# mk312lite_V2.net
KiCad netlist of a schematic drawn in EAGLE
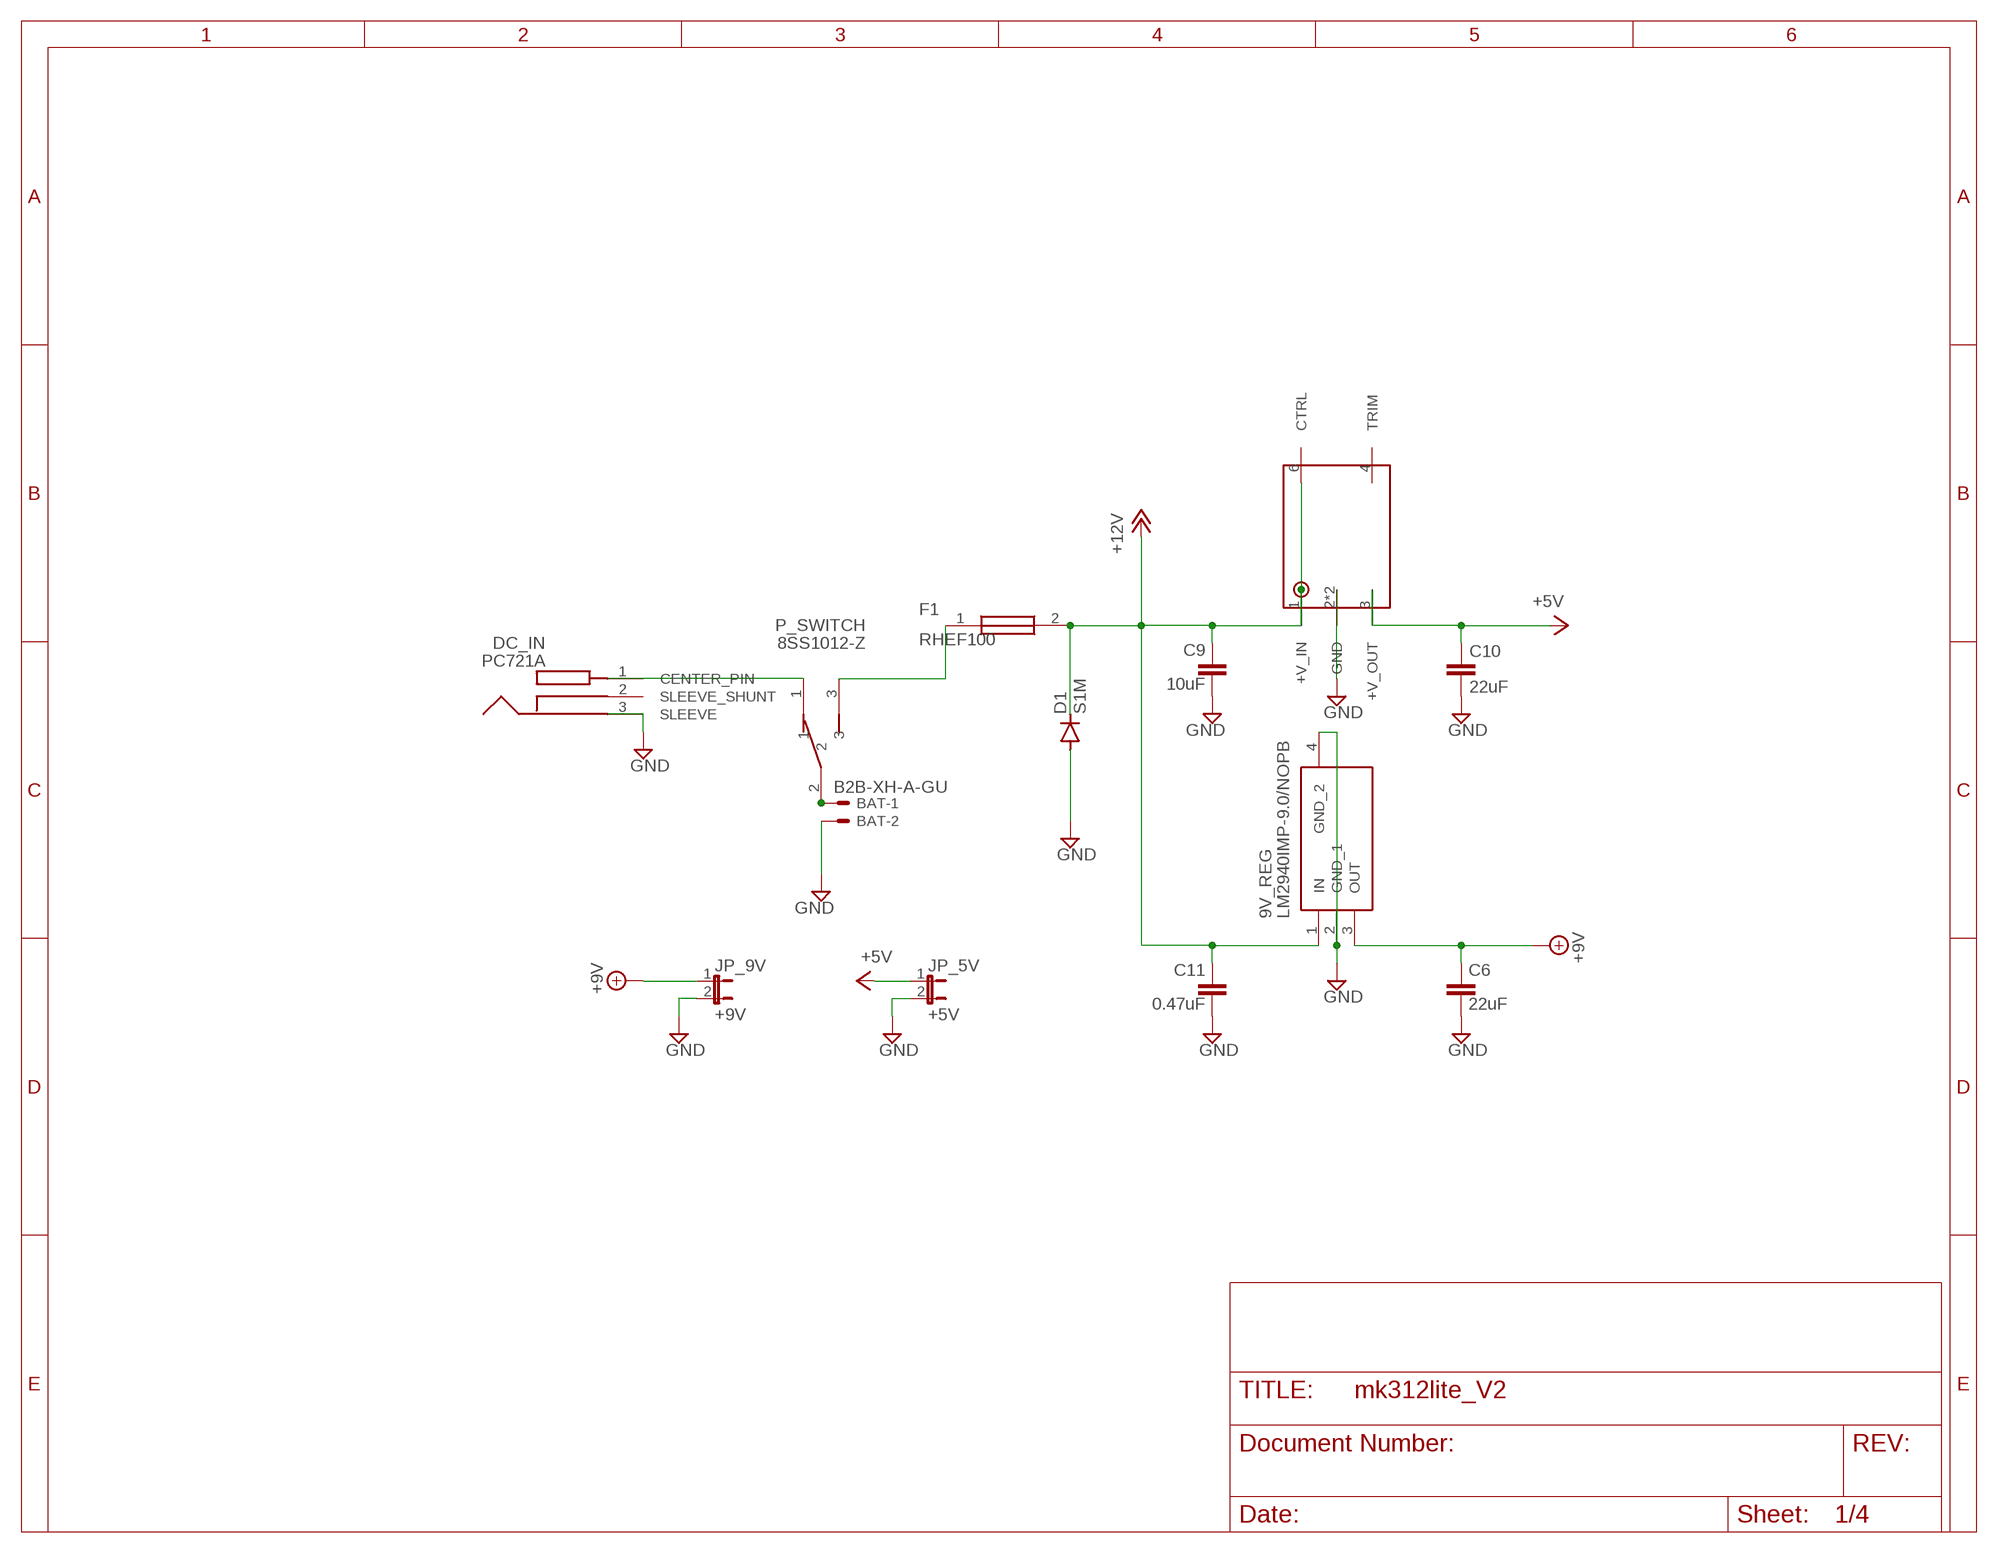
[diagram p0: schematic, sheet 1]
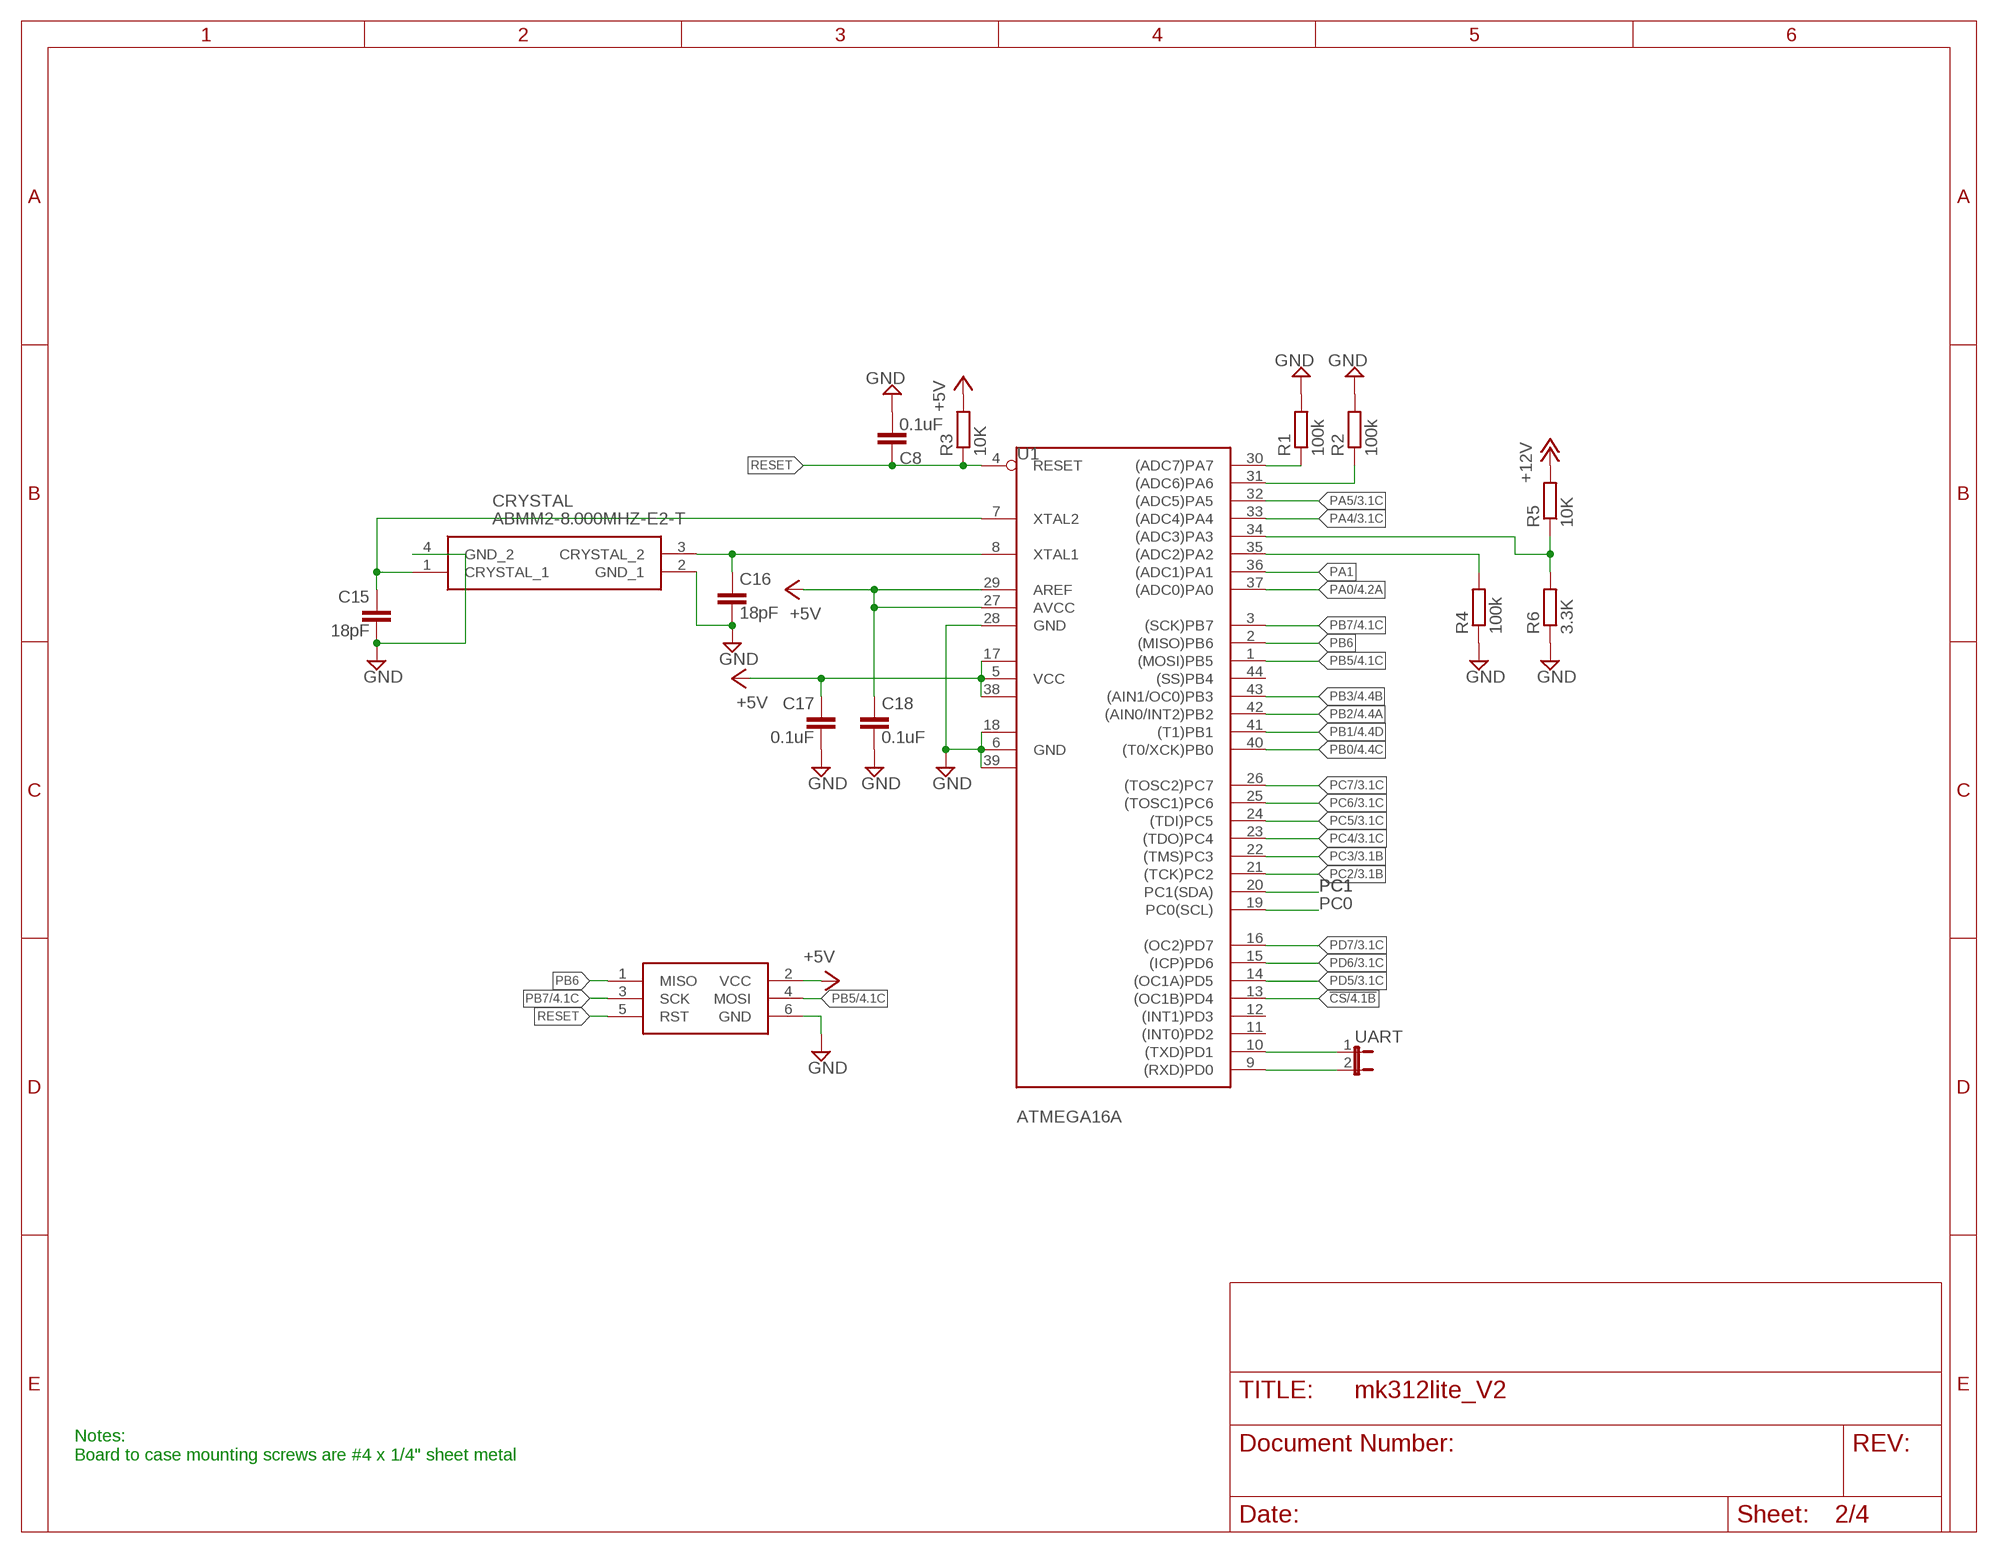
[diagram p1: schematic, sheet 2]
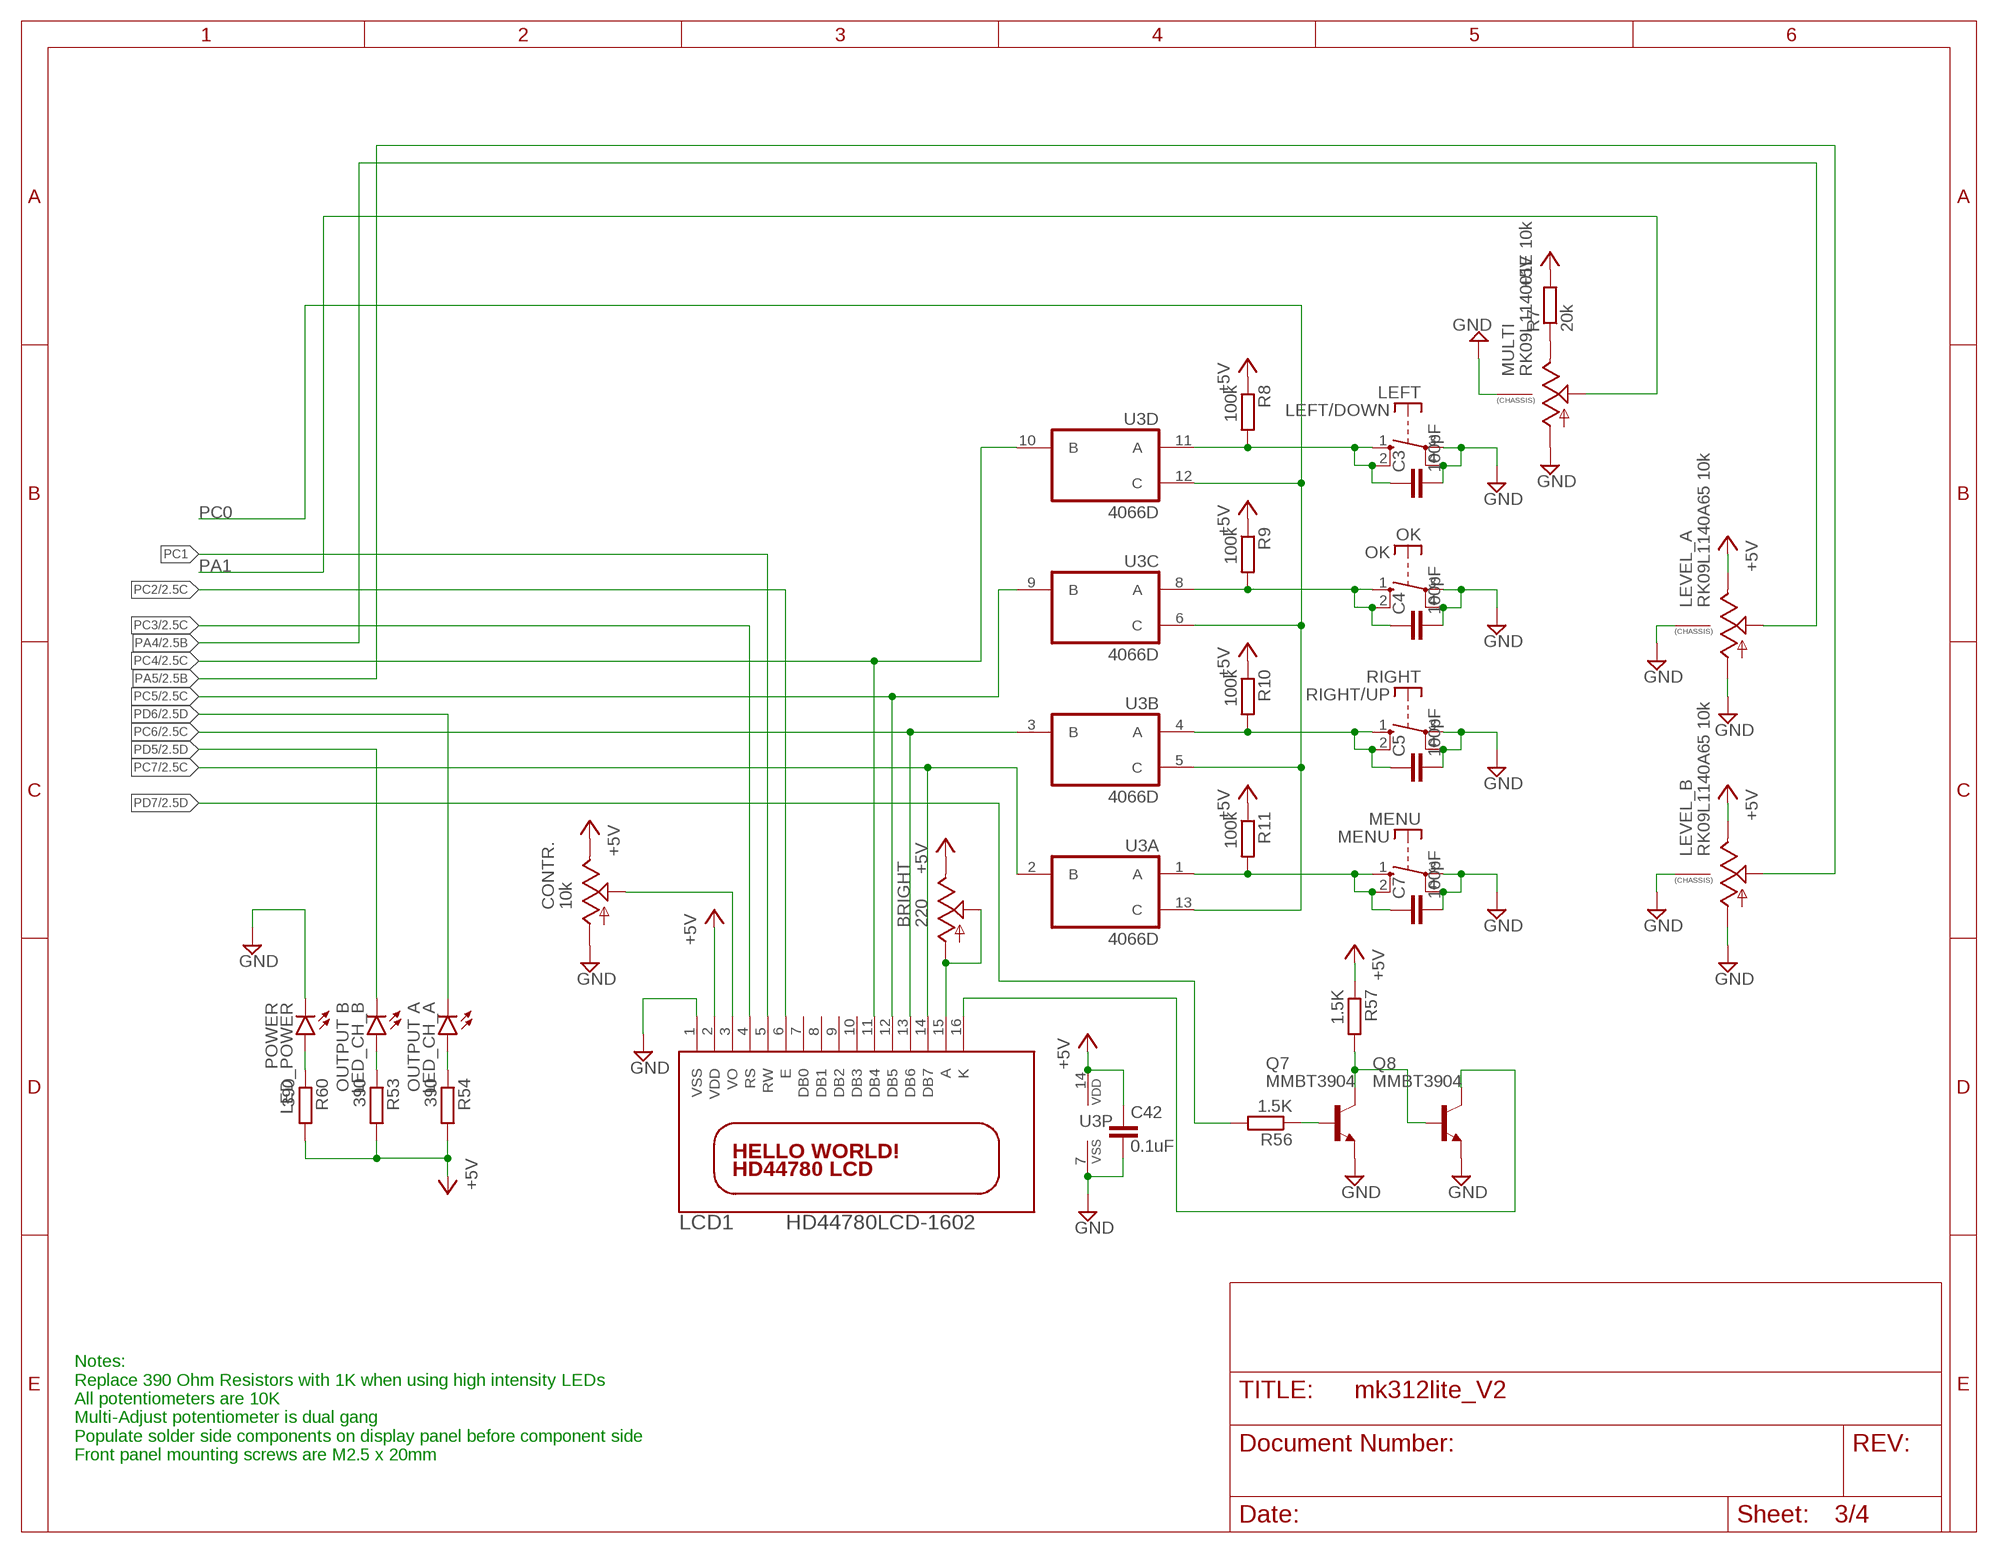
[diagram p2: schematic, sheet 3]
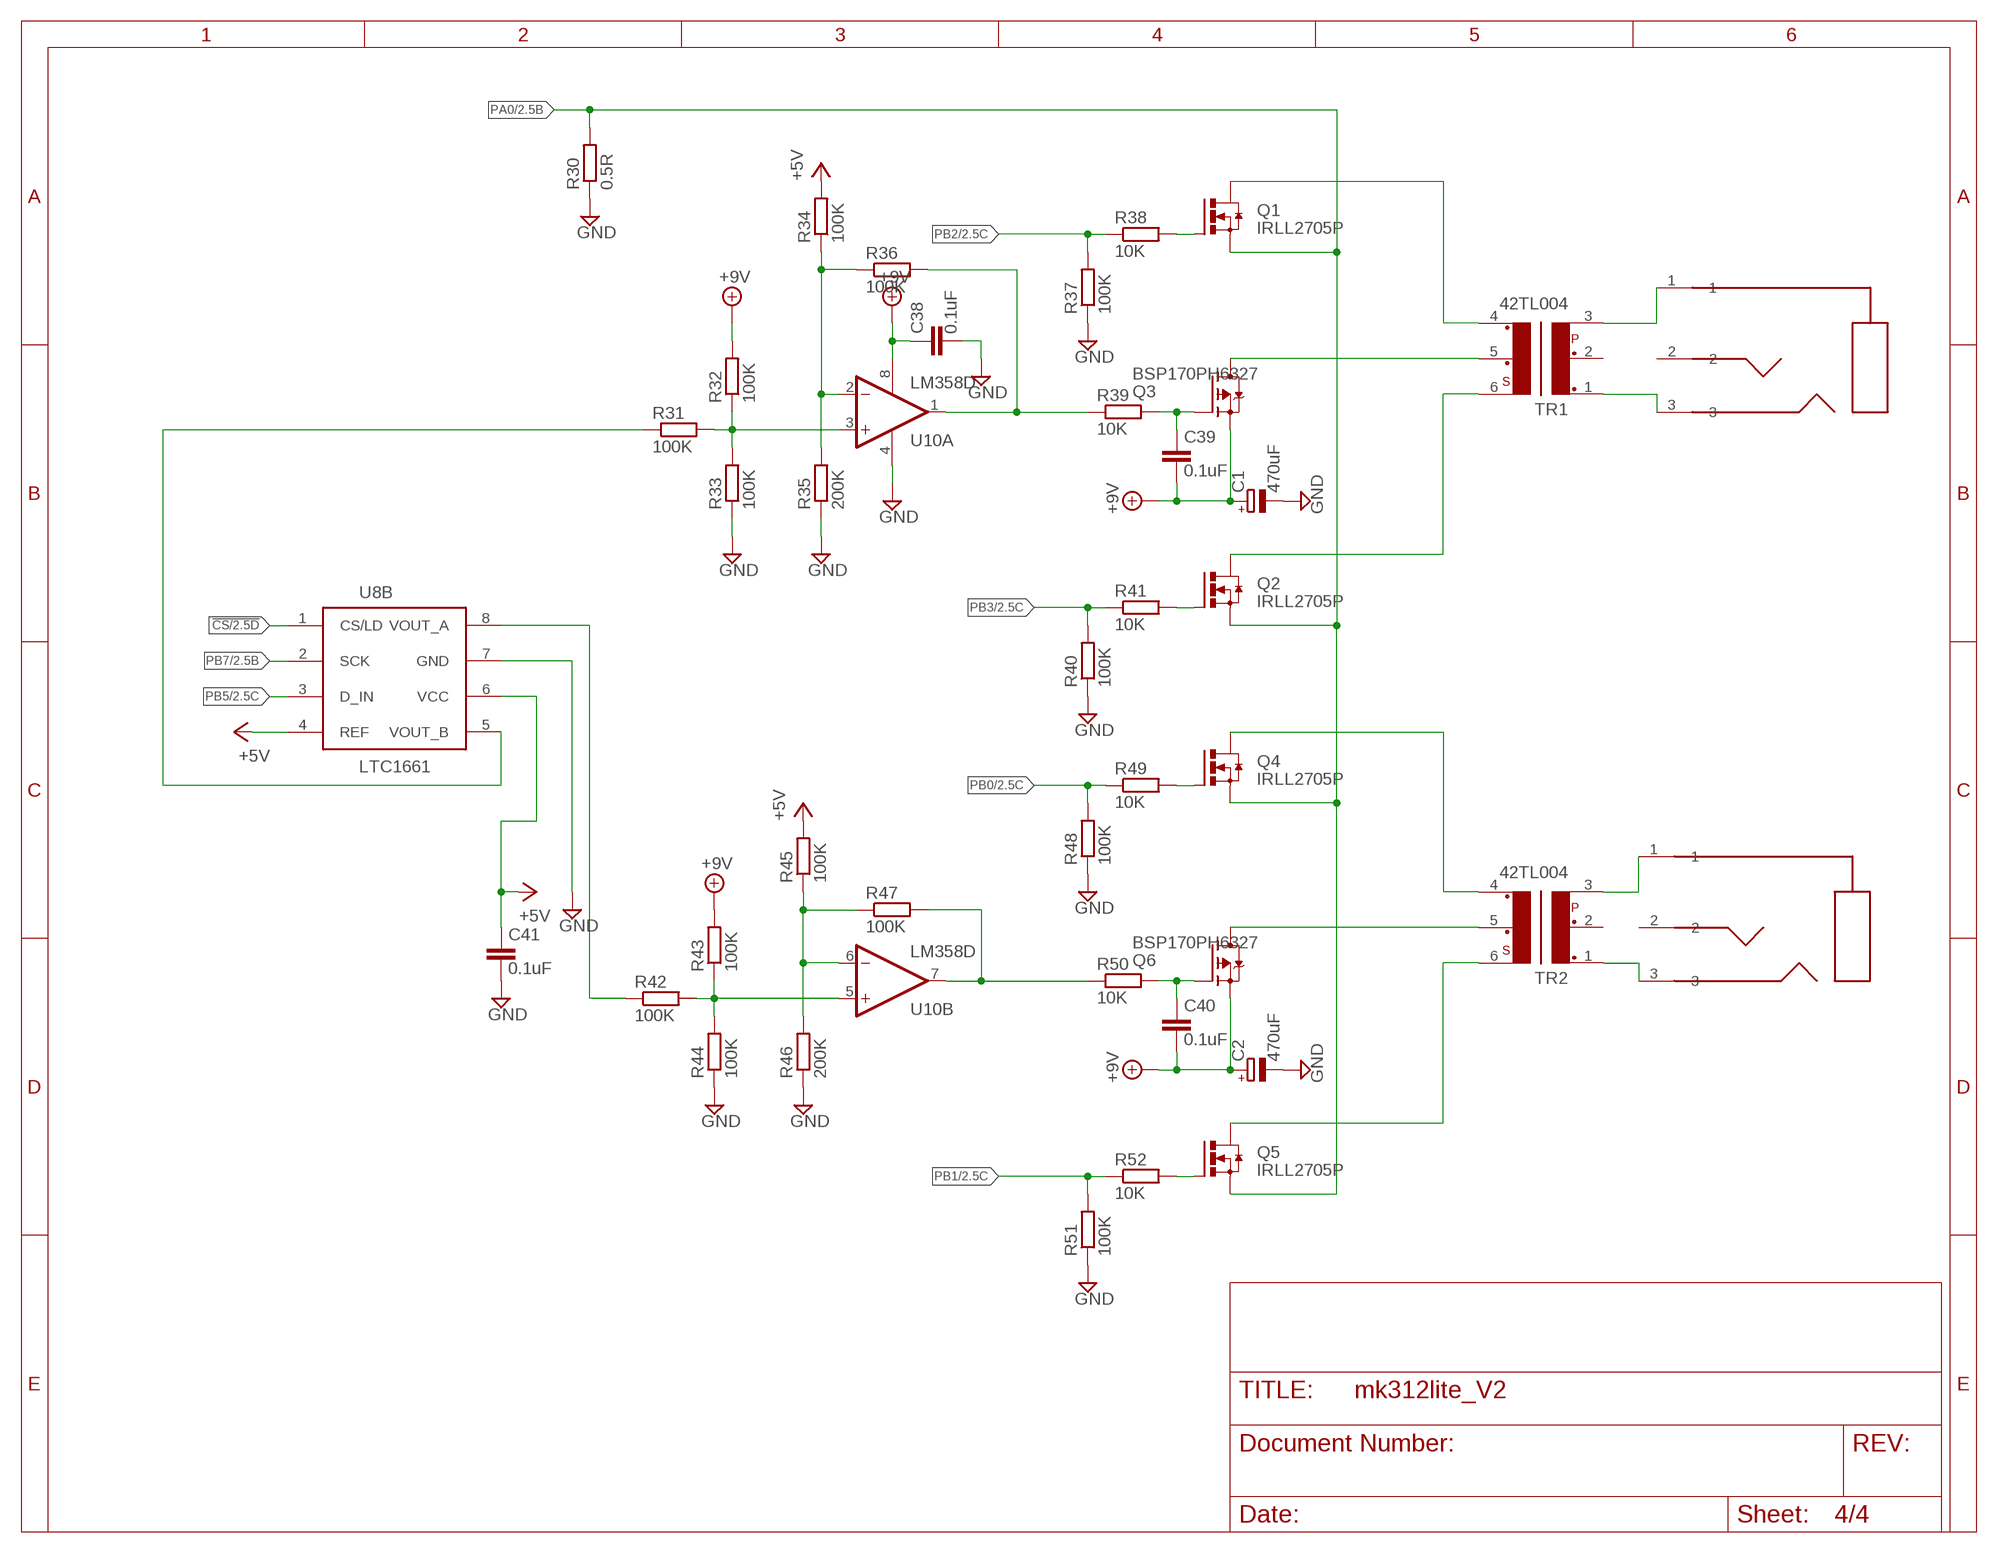
[diagram p3: schematic, sheet 4]

(export (version "E")
  (design (tool "Eeschema 10.0.6"))
  (components
    (comp (ref "C8")
      (value "0.1uF")
      (footprint "eagle-import:C0805")
      (libsource (lib "eagle-import") (part "C-EUC0805"))
    )
    (comp (ref "C15")
      (value "18pF")
      (footprint "eagle-import:C0805")
      (libsource (lib "eagle-import") (part "C-EUC0805"))
    )
    (comp (ref "C16")
      (value "18pF")
      (footprint "eagle-import:C0805")
      (libsource (lib "eagle-import") (part "C-EUC0805"))
    )
    (comp (ref "C17")
      (value "0.1uF")
      (footprint "eagle-import:C0805")
      (libsource (lib "eagle-import") (part "C-EUC0805"))
    )
    (comp (ref "C18")
      (value "0.1uF")
      (footprint "eagle-import:C0805")
      (libsource (lib "eagle-import") (part "C-EUC0805"))
    )
    (comp (ref "CRYSTAL")
      (value "ABMM2-8.000MHZ-E2-T")
      (footprint "eagle-import:ABMM2")
      (fields (field (name "MOUSER_PART_NUMBER") "815-ABMM2-8-E2T"))
      (libsource (lib "eagle-import") (part "ABMM2-8.000MHZ-E2-T"))
    )
    (comp (ref "ISP1")
      (value "AVRISP-6")
      (footprint "eagle-import:AVRISP")
      (libsource (lib "eagle-import") (part "AVRISP-6"))
    )
    (comp (ref "R1")
      (value "100k")
      (footprint "eagle-import:R0805")
      (libsource (lib "eagle-import") (part "R-EU_R0805"))
    )
    (comp (ref "R2")
      (value "100k")
      (footprint "eagle-import:R0805")
      (libsource (lib "eagle-import") (part "R-EU_R0805"))
    )
    (comp (ref "R3")
      (value "10K")
      (footprint "eagle-import:R0805")
      (libsource (lib "eagle-import") (part "R-EU_R0805"))
    )
    (comp (ref "R4")
      (value "100k")
      (footprint "eagle-import:R0805")
      (libsource (lib "eagle-import") (part "R-EU_R0805"))
    )
    (comp (ref "R5")
      (value "10K")
      (footprint "eagle-import:R0805")
      (libsource (lib "eagle-import") (part "R-EU_R0805"))
    )
    (comp (ref "R6")
      (value "3.3K")
      (footprint "eagle-import:R0805")
      (libsource (lib "eagle-import") (part "R-EU_R0805"))
    )
    (comp (ref "U1")
      (value "ATMEGA16A")
      (footprint "eagle-import:TQFP44")
      (fields (field (name "MPN") "ATMEGA16-16AU"))
      (libsource (lib "eagle-import") (part "MEGA16-A"))
    )
    (comp (ref "UART")
      (value "JP1E")
      (footprint "eagle-import:JP1")
      (libsource (lib "eagle-import") (part "jumper_252_JP1E"))
    )
    (comp (ref "C1")
      (value "470uF")
      (footprint "eagle-import:150CLZ-1010")
      (libsource (lib "eagle-import") (part "CPOL-EU150CLZ-1010"))
    )
    (comp (ref "C2")
      (value "470uF")
      (footprint "eagle-import:150CLZ-1010")
      (libsource (lib "eagle-import") (part "CPOL-EU150CLZ-1010"))
    )
    (comp (ref "C38")
      (value "0.1uF")
      (footprint "eagle-import:C0805")
      (libsource (lib "eagle-import") (part "C-EUC0805"))
    )
    (comp (ref "C39")
      (value "0.1uF")
      (footprint "eagle-import:C0805")
      (libsource (lib "eagle-import") (part "C-EUC0805"))
    )
    (comp (ref "C40")
      (value "0.1uF")
      (footprint "eagle-import:C0805")
      (libsource (lib "eagle-import") (part "C-EUC0805"))
    )
    (comp (ref "C41")
      (value "0.1uF")
      (footprint "eagle-import:C0805")
      (libsource (lib "eagle-import") (part "C-EUC0805"))
    )
    (comp (ref "CHAN_A")
      (value "PJ-301C")
      (footprint "eagle-import:PJ-301C")
      (libsource (lib "eagle-import") (part "PC-301C"))
    )
    (comp (ref "CHAN_B")
      (value "PJ-301C")
      (footprint "eagle-import:PJ-301C")
      (libsource (lib "eagle-import") (part "PC-301C"))
    )
    (comp (ref "Q1")
      (value "IRLL2705P")
      (footprint "eagle-import:SOT223")
      (libsource (lib "eagle-import") (part "N-HEXFET-2D_?-SOT232IRLL2705"))
    )
    (comp (ref "Q2")
      (value "IRLL2705P")
      (footprint "eagle-import:SOT223")
      (libsource (lib "eagle-import") (part "N-HEXFET-2D_?-SOT232IRLL2705"))
    )
    (comp (ref "Q3")
      (value "BSP170PH6327")
      (footprint "eagle-import:SOT230P700X180-4N")
      (libsource (lib "eagle-import") (part "IRFL9014TRPBF"))
    )
    (comp (ref "Q4")
      (value "IRLL2705P")
      (footprint "eagle-import:SOT223")
      (libsource (lib "eagle-import") (part "N-HEXFET-2D_?-SOT232IRLL2705"))
    )
    (comp (ref "Q5")
      (value "IRLL2705P")
      (footprint "eagle-import:SOT223")
      (libsource (lib "eagle-import") (part "N-HEXFET-2D_?-SOT232IRLL2705"))
    )
    (comp (ref "Q6")
      (value "BSP170PH6327")
      (footprint "eagle-import:SOT230P700X180-4N")
      (libsource (lib "eagle-import") (part "IRFL9014TRPBF"))
    )
    (comp (ref "R30")
      (value "0.5R")
      (footprint "eagle-import:R1210")
      (libsource (lib "eagle-import") (part "R-EU_R1210"))
    )
    (comp (ref "R31")
      (value "100K")
      (footprint "eagle-import:R0805")
      (libsource (lib "eagle-import") (part "R-EU_R0805"))
    )
    (comp (ref "R32")
      (value "100K")
      (footprint "eagle-import:R0805")
      (libsource (lib "eagle-import") (part "R-EU_R0805"))
    )
    (comp (ref "R33")
      (value "100K")
      (footprint "eagle-import:R0805")
      (libsource (lib "eagle-import") (part "R-EU_R0805"))
    )
    (comp (ref "R34")
      (value "100K")
      (footprint "eagle-import:R0805")
      (libsource (lib "eagle-import") (part "R-EU_R0805"))
    )
    (comp (ref "R35")
      (value "200K")
      (footprint "eagle-import:R0805")
      (libsource (lib "eagle-import") (part "R-EU_R0805"))
    )
    (comp (ref "R36")
      (value "100K")
      (footprint "eagle-import:R0805")
      (libsource (lib "eagle-import") (part "R-EU_R0805"))
    )
    (comp (ref "R37")
      (value "100K")
      (footprint "eagle-import:R0805")
      (libsource (lib "eagle-import") (part "R-EU_R0805"))
    )
    (comp (ref "R38")
      (value "10K")
      (footprint "eagle-import:R0805")
      (libsource (lib "eagle-import") (part "R-EU_R0805"))
    )
    (comp (ref "R39")
      (value "10K")
      (footprint "eagle-import:R0805")
      (libsource (lib "eagle-import") (part "R-EU_R0805"))
    )
    (comp (ref "R40")
      (value "100K")
      (footprint "eagle-import:R0805")
      (libsource (lib "eagle-import") (part "R-EU_R0805"))
    )
    (comp (ref "R41")
      (value "10K")
      (footprint "eagle-import:R0805")
      (libsource (lib "eagle-import") (part "R-EU_R0805"))
    )
    (comp (ref "R42")
      (value "100K")
      (footprint "eagle-import:R0805")
      (libsource (lib "eagle-import") (part "R-EU_R0805"))
    )
    (comp (ref "R43")
      (value "100K")
      (footprint "eagle-import:R0805")
      (libsource (lib "eagle-import") (part "R-EU_R0805"))
    )
    (comp (ref "R44")
      (value "100K")
      (footprint "eagle-import:R0805")
      (libsource (lib "eagle-import") (part "R-EU_R0805"))
    )
    (comp (ref "R45")
      (value "100K")
      (footprint "eagle-import:R0805")
      (libsource (lib "eagle-import") (part "R-EU_R0805"))
    )
    (comp (ref "R46")
      (value "200K")
      (footprint "eagle-import:R0805")
      (libsource (lib "eagle-import") (part "R-EU_R0805"))
    )
    (comp (ref "R47")
      (value "100K")
      (footprint "eagle-import:R0805")
      (libsource (lib "eagle-import") (part "R-EU_R0805"))
    )
    (comp (ref "R48")
      (value "100K")
      (footprint "eagle-import:R0805")
      (libsource (lib "eagle-import") (part "R-EU_R0805"))
    )
    (comp (ref "R49")
      (value "10K")
      (footprint "eagle-import:R0805")
      (libsource (lib "eagle-import") (part "R-EU_R0805"))
    )
    (comp (ref "R50")
      (value "10K")
      (footprint "eagle-import:R0805")
      (libsource (lib "eagle-import") (part "R-EU_R0805"))
    )
    (comp (ref "R51")
      (value "100K")
      (footprint "eagle-import:R0805")
      (libsource (lib "eagle-import") (part "R-EU_R0805"))
    )
    (comp (ref "R52")
      (value "10K")
      (footprint "eagle-import:R0805")
      (libsource (lib "eagle-import") (part "R-EU_R0805"))
    )
    (comp (ref "TR1")
      (value "42TL004")
      (footprint "eagle-import:42TL")
      (libsource (lib "eagle-import") (part "42T?L023"))
    )
    (comp (ref "TR2")
      (value "42TL004")
      (footprint "eagle-import:42TL")
      (libsource (lib "eagle-import") (part "42T?L023"))
    )
    (comp (ref "U8B")
      (value "LTC1661")
      (footprint "eagle-import:MSOP8")
      (libsource (lib "eagle-import") (part "LTC1661IMS8"))
    )
    (comp (ref "U10")
      (value "LM358D")
      (footprint "eagle-import:SO08")
      (libsource (lib "eagle-import") (part "LM358D"))
    )
    (comp (ref "9V_REG")
      (value "LM2940IMP-9.0/NOPB")
      (footprint "eagle-import:SOT230P700X180-4N")
      (fields (field (name "MOUSER_PART_NUMBER") "926-LM2940IMP90NOPB"))
      (libsource (lib "eagle-import") (part "LM2940IMP-9.0_NOPB"))
    )
    (comp (ref "BAT")
      (value "B2B-XH-A-GU")
      (footprint "eagle-import:JST-XH-02-PACKAGE-LONG-PAD")
      (libsource (lib "eagle-import") (part "JST-XH-02-PIN-LONG-PAD"))
    )
    (comp (ref "C6")
      (value "22uF")
      (footprint "eagle-import:C1206")
      (libsource (lib "eagle-import") (part "C-EUC1206"))
    )
    (comp (ref "C9")
      (value "10uF")
      (footprint "eagle-import:C0805")
      (libsource (lib "eagle-import") (part "C-EUC0805"))
    )
    (comp (ref "C10")
      (value "22uF")
      (footprint "eagle-import:C1206")
      (libsource (lib "eagle-import") (part "C-EUC1206"))
    )
    (comp (ref "C11")
      (value "0.47uF")
      (footprint "eagle-import:C0805")
      (libsource (lib "eagle-import") (part "C-EUC0805"))
    )
    (comp (ref "D1")
      (value "S1M")
      (footprint "eagle-import:SMA")
      (libsource (lib "eagle-import") (part "S1M"))
    )
    (comp (ref "DC_IN")
      (value "PC721A")
      (footprint "eagle-import:PC721A")
      (fields (field (name "MOUSER_PART_NUMBER") "502-PC721A"))
      (libsource (lib "eagle-import") (part "PC721A"))
    )
    (comp (ref "F1")
      (value "RHEF100")
      (footprint "eagle-import:RHEF1002")
      (fields
        (field (name "MANUFACTURER_PART_NUMBER") "RHEF100-2")
        (field (name "MOUSER_PART_NUMBER") "650-RHEF100-2")
      )
      (libsource (lib "eagle-import") (part "RHEF100-2"))
    )
    (comp (ref "JP_5V")
      (value "+5V")
      (footprint "eagle-import:JP1")
      (libsource (lib "eagle-import") (part "JP1E"))
    )
    (comp (ref "JP_9V")
      (value "+9V")
      (footprint "eagle-import:JP1")
      (libsource (lib "eagle-import") (part "JP1E"))
    )
    (comp (ref "P_SWITCH")
      (value "8SS1012-Z")
      (footprint "eagle-import:8SS1012Z")
      (libsource (lib "eagle-import") (part "8SS1012-Z"))
    )
    (comp (ref "U$1")
      (value "K7805MT-500R4")
      (footprint "eagle-import:DFN")
      (libsource (lib "eagle-import") (part "K7805MT-500R4"))
    )
    (comp (ref "BRIGHT")
      (value "220")
      (footprint "eagle-import:B25P")
      (libsource (lib "eagle-import") (part "TRIM_US-B25P"))
    )
    (comp (ref "C3")
      (value "100pF")
      (footprint "eagle-import:C0805")
      (libsource (lib "eagle-import") (part "C-EUC0805"))
    )
    (comp (ref "C4")
      (value "100pF")
      (footprint "eagle-import:C0805")
      (libsource (lib "eagle-import") (part "C-EUC0805"))
    )
    (comp (ref "C5")
      (value "100pF")
      (footprint "eagle-import:C0805")
      (libsource (lib "eagle-import") (part "C-EUC0805"))
    )
    (comp (ref "C7")
      (value "100pF")
      (footprint "eagle-import:C0805")
      (libsource (lib "eagle-import") (part "C-EUC0805"))
    )
    (comp (ref "C42")
      (value "0.1uF")
      (footprint "eagle-import:C0805")
      (libsource (lib "eagle-import") (part "C-EUC0805"))
    )
    (comp (ref "CONTR.")
      (value "10k")
      (footprint "eagle-import:B25P")
      (libsource (lib "eagle-import") (part "TRIM_US-B25P"))
    )
    (comp (ref "LCD1")
      (value "HD44780LCD-1602")
      (footprint "eagle-import:LCD1602")
      (libsource (lib "eagle-import") (part "HD44780LCD-1602"))
    )
    (comp (ref "LED_CH_A")
      (value "OUTPUT A")
      (footprint "eagle-import:LED3MM")
      (libsource (lib "eagle-import") (part "LED3MM"))
    )
    (comp (ref "LED_CH_B")
      (value "OUTPUT B")
      (footprint "eagle-import:LED3MM")
      (libsource (lib "eagle-import") (part "LED3MM"))
    )
    (comp (ref "LED_POWER")
      (value "POWER")
      (footprint "eagle-import:LED3MM")
      (libsource (lib "eagle-import") (part "LED3MM"))
    )
    (comp (ref "LEFT")
      (value "LEFT/DOWN")
      (footprint "eagle-import:DTE6K")
      (libsource (lib "eagle-import") (part "DTE6K"))
    )
    (comp (ref "LEVEL_A")
      (value "RK09L1140A65 10k")
      (footprint "eagle-import:9MM_SNAP-IN_POT")
      (libsource (lib "eagle-import") (part "9MM_SNAP-IN_POT_CHASSIS"))
    )
    (comp (ref "LEVEL_B")
      (value "RK09L1140A65 10k")
      (footprint "eagle-import:9MM_SNAP-IN_POT")
      (libsource (lib "eagle-import") (part "9MM_SNAP-IN_POT_CHASSIS"))
    )
    (comp (ref "MENU")
      (value "MENU")
      (footprint "eagle-import:DTE6K")
      (libsource (lib "eagle-import") (part "DTE6K"))
    )
    (comp (ref "MULTI")
      (value "RK09L114001E 10k")
      (footprint "eagle-import:9MM_SNAP-IN_POT")
      (libsource (lib "eagle-import") (part "9MM_SNAP-IN_POT_CHASSIS"))
    )
    (comp (ref "OK")
      (value "OK")
      (footprint "eagle-import:DTE6K")
      (libsource (lib "eagle-import") (part "DTE6K"))
    )
    (comp (ref "Q7")
      (value "MMBT3904")
      (footprint "eagle-import:SOT23-BEC")
      (libsource (lib "eagle-import") (part "-NPN-SOT23-BECMMBT3904LT1"))
    )
    (comp (ref "Q8")
      (value "MMBT3904")
      (footprint "eagle-import:SOT23-BEC")
      (libsource (lib "eagle-import") (part "-NPN-SOT23-BECMMBT3904LT1"))
    )
    (comp (ref "R7")
      (value "20k")
      (footprint "eagle-import:R0805")
      (libsource (lib "eagle-import") (part "R-EU_R0805"))
    )
    (comp (ref "R8")
      (value "100k")
      (footprint "eagle-import:R0805")
      (libsource (lib "eagle-import") (part "R-EU_R0805"))
    )
    (comp (ref "R9")
      (value "100k")
      (footprint "eagle-import:R0805")
      (libsource (lib "eagle-import") (part "R-EU_R0805"))
    )
    (comp (ref "R10")
      (value "100k")
      (footprint "eagle-import:R0805")
      (libsource (lib "eagle-import") (part "R-EU_R0805"))
    )
    (comp (ref "R11")
      (value "100k")
      (footprint "eagle-import:R0805")
      (libsource (lib "eagle-import") (part "R-EU_R0805"))
    )
    (comp (ref "R53")
      (value "390")
      (footprint "eagle-import:R0805")
      (libsource (lib "eagle-import") (part "R-EU_R0805"))
    )
    (comp (ref "R54")
      (value "390")
      (footprint "eagle-import:R0805")
      (libsource (lib "eagle-import") (part "R-EU_R0805"))
    )
    (comp (ref "R56")
      (value "1.5K")
      (footprint "eagle-import:R0805")
      (libsource (lib "eagle-import") (part "R-EU_R0805"))
    )
    (comp (ref "R57")
      (value "1.5K")
      (footprint "eagle-import:R0805")
      (libsource (lib "eagle-import") (part "R-EU_R0805"))
    )
    (comp (ref "R60")
      (value "390")
      (footprint "eagle-import:R0805")
      (libsource (lib "eagle-import") (part "R-EU_R0805"))
    )
    (comp (ref "RIGHT")
      (value "RIGHT/UP")
      (footprint "eagle-import:DTE6K")
      (libsource (lib "eagle-import") (part "DTE6K"))
    )
    (comp (ref "U3")
      (value "4066D")
      (footprint "eagle-import:SO14")
      (libsource (lib "eagle-import") (part "4066D"))
    )
  )
  (nets
    (net (code "1") (name "+5V") (class "Default")
      (node (ref "BRIGHT") (pin "E") (pinfunction "E_E") (pintype "passive"))
      (node (ref "C10") (pin "1") (pinfunction "1_1") (pintype "passive"))
      (node (ref "C17") (pin "1") (pinfunction "1_1") (pintype "passive"))
      (node (ref "C18") (pin "1") (pinfunction "1_1") (pintype "passive"))
      (node (ref "C41") (pin "1") (pinfunction "1_1") (pintype "passive"))
      (node (ref "C42") (pin "1") (pinfunction "1_1") (pintype "passive"))
      (node (ref "CONTR.") (pin "E") (pinfunction "E_E") (pintype "passive"))
      (node (ref "ISP1") (pin "2") (pinfunction "VCC_2") (pintype "power_in"))
      (node (ref "JP_5V") (pin "1") (pinfunction "1_1") (pintype "passive"))
      (node (ref "LCD1") (pin "2") (pinfunction "VDD_2") (pintype "power_in"))
      (node (ref "LEVEL_A") (pin "3") (pinfunction "E_3") (pintype "passive"))
      (node (ref "LEVEL_B") (pin "3") (pinfunction "E_3") (pintype "passive"))
      (node (ref "R10") (pin "1") (pinfunction "1_1") (pintype "passive"))
      (node (ref "R11") (pin "1") (pinfunction "1_1") (pintype "passive"))
      (node (ref "R3") (pin "2") (pinfunction "2_2") (pintype "passive"))
      (node (ref "R34") (pin "2") (pinfunction "2_2") (pintype "passive"))
      (node (ref "R45") (pin "2") (pinfunction "2_2") (pintype "passive"))
      (node (ref "R53") (pin "2") (pinfunction "2_2") (pintype "passive"))
      (node (ref "R54") (pin "2") (pinfunction "2_2") (pintype "passive"))
      (node (ref "R57") (pin "1") (pinfunction "1_1") (pintype "passive"))
      (node (ref "R60") (pin "2") (pinfunction "2_2") (pintype "passive"))
      (node (ref "R7") (pin "2") (pinfunction "2_2") (pintype "passive"))
      (node (ref "R8") (pin "1") (pinfunction "1_1") (pintype "passive"))
      (node (ref "R9") (pin "1") (pinfunction "1_1") (pintype "passive"))
      (node (ref "U$1") (pin "3") (pinfunction "+V_OUT_3") (pintype "output"))
      (node (ref "U1") (pin "17") (pinfunction "VCC1_17") (pintype "power_in"))
      (node (ref "U1") (pin "27") (pinfunction "AVCC_27") (pintype "power_in"))
      (node (ref "U1") (pin "29") (pinfunction "AREF_29") (pintype "passive"))
      (node (ref "U1") (pin "38") (pinfunction "VCC2_38") (pintype "power_in"))
      (node (ref "U1") (pin "5") (pinfunction "VCC_5") (pintype "power_in"))
      (node (ref "U3") (pin "14") (pinfunction "VDD_14") (pintype "power_in"))
      (node (ref "U8B") (pin "4") (pinfunction "REF_4") (pintype "input"))
      (node (ref "U8B") (pin "6") (pinfunction "VCC_6") (pintype "power_in"))
    )
    (net (code "2") (name "+9V") (class "Default")
      (node (ref "9V_REG") (pin "3") (pinfunction "OUT_3") (pintype "bidirectional"))
      (node (ref "C1") (pin "+") (pinfunction "+_+") (pintype "passive"))
      (node (ref "C2") (pin "+") (pinfunction "+_+") (pintype "passive"))
      (node (ref "C38") (pin "1") (pinfunction "1_1") (pintype "passive"))
      (node (ref "C39") (pin "2") (pinfunction "2_2") (pintype "passive"))
      (node (ref "C40") (pin "2") (pinfunction "2_2") (pintype "passive"))
      (node (ref "C6") (pin "1") (pinfunction "1_1") (pintype "passive"))
      (node (ref "JP_9V") (pin "1") (pinfunction "1_1") (pintype "passive"))
      (node (ref "Q3") (pin "3") (pinfunction "S_3") (pintype "passive"))
      (node (ref "Q6") (pin "3") (pinfunction "S_3") (pintype "passive"))
      (node (ref "R32") (pin "2") (pinfunction "2_2") (pintype "passive"))
      (node (ref "R43") (pin "2") (pinfunction "2_2") (pintype "passive"))
      (node (ref "U10") (pin "8") (pinfunction "V+_8") (pintype "power_in"))
    )
    (net (code "3") (name "+12V") (class "Default")
      (node (ref "9V_REG") (pin "1") (pinfunction "IN_1") (pintype "bidirectional"))
      (node (ref "C11") (pin "1") (pinfunction "1_1") (pintype "passive"))
      (node (ref "C9") (pin "1") (pinfunction "1_1") (pintype "passive"))
      (node (ref "D1") (pin "C") (pinfunction "C_C") (pintype "passive"))
      (node (ref "F1") (pin "2") (pinfunction "2_2") (pintype "bidirectional"))
      (node (ref "R5") (pin "2") (pinfunction "2_2") (pintype "passive"))
      (node (ref "U$1") (pin "1") (pinfunction "+V_IN_1") (pintype "input"))
      (node (ref "U$1") (pin "6") (pinfunction "CTRL_6") (pintype "input"))
    )
    (net (code "4") (name "GND") (class "Default")
      (node (ref "9V_REG") (pin "2") (pinfunction "GND_1_2") (pintype "bidirectional"))
      (node (ref "9V_REG") (pin "4") (pinfunction "GND_2_4") (pintype "bidirectional"))
      (node (ref "BAT") (pin "2") (pinfunction "S_2") (pintype "passive"))
      (node (ref "C1") (pin "-") (pinfunction "-_-") (pintype "passive"))
      (node (ref "C10") (pin "2") (pinfunction "2_2") (pintype "passive"))
      (node (ref "C11") (pin "2") (pinfunction "2_2") (pintype "passive"))
      (node (ref "C15") (pin "2") (pinfunction "2_2") (pintype "passive"))
      (node (ref "C16") (pin "2") (pinfunction "2_2") (pintype "passive"))
      (node (ref "C17") (pin "2") (pinfunction "2_2") (pintype "passive"))
      (node (ref "C18") (pin "2") (pinfunction "2_2") (pintype "passive"))
      (node (ref "C2") (pin "-") (pinfunction "-_-") (pintype "passive"))
      (node (ref "C3") (pin "2") (pinfunction "2_2") (pintype "passive"))
      (node (ref "C38") (pin "2") (pinfunction "2_2") (pintype "passive"))
      (node (ref "C4") (pin "2") (pinfunction "2_2") (pintype "passive"))
      (node (ref "C41") (pin "2") (pinfunction "2_2") (pintype "passive"))
      (node (ref "C42") (pin "2") (pinfunction "2_2") (pintype "passive"))
      (node (ref "C5") (pin "2") (pinfunction "2_2") (pintype "passive"))
      (node (ref "C6") (pin "2") (pinfunction "2_2") (pintype "passive"))
      (node (ref "C7") (pin "2") (pinfunction "2_2") (pintype "passive"))
      (node (ref "C8") (pin "2") (pinfunction "2_2") (pintype "passive"))
      (node (ref "C9") (pin "2") (pinfunction "2_2") (pintype "passive"))
      (node (ref "CONTR.") (pin "A") (pinfunction "A_A") (pintype "passive"))
      (node (ref "CRYSTAL") (pin "2") (pinfunction "GND_1_2") (pintype "bidirectional"))
      (node (ref "CRYSTAL") (pin "4") (pinfunction "GND_2_4") (pintype "bidirectional"))
      (node (ref "D1") (pin "A") (pinfunction "A_A") (pintype "passive"))
      (node (ref "DC_IN") (pin "3") (pinfunction "SLEEVE_3") (pintype "bidirectional"))
      (node (ref "ISP1") (pin "6") (pinfunction "GND_6") (pintype "power_in"))
      (node (ref "JP_5V") (pin "2") (pinfunction "2_2") (pintype "passive"))
      (node (ref "JP_9V") (pin "2") (pinfunction "2_2") (pintype "passive"))
      (node (ref "LCD1") (pin "1") (pinfunction "VSS_1") (pintype "power_in"))
      (node (ref "LED_POWER") (pin "K") (pinfunction "C_K") (pintype "passive"))
      (node (ref "LEFT") (pin "3") (pinfunction "P_3") (pintype "passive"))
      (node (ref "LEFT") (pin "4") (pinfunction "P_4") (pintype "passive"))
      (node (ref "LEVEL_A") (pin "1") (pinfunction "A_1") (pintype "passive"))
      (node (ref "LEVEL_A") (pin "CHASSIS2") (pinfunction "P$1_CHASSIS2") (pintype "passive"))
      (node (ref "LEVEL_B") (pin "1") (pinfunction "A_1") (pintype "passive"))
      (node (ref "LEVEL_B") (pin "CHASSIS2") (pinfunction "P$1_CHASSIS2") (pintype "passive"))
      (node (ref "MENU") (pin "3") (pinfunction "P_3") (pintype "passive"))
      (node (ref "MENU") (pin "4") (pinfunction "P_4") (pintype "passive"))
      (node (ref "MULTI") (pin "1") (pinfunction "A_1") (pintype "passive"))
      (node (ref "MULTI") (pin "CHASSIS2") (pinfunction "P$1_CHASSIS2") (pintype "passive"))
      (node (ref "OK") (pin "3") (pinfunction "P_3") (pintype "passive"))
      (node (ref "OK") (pin "4") (pinfunction "P_4") (pintype "passive"))
      (node (ref "Q7") (pin "E") (pinfunction "E_E") (pintype "passive"))
      (node (ref "Q8") (pin "E") (pinfunction "E_E") (pintype "passive"))
      (node (ref "R1") (pin "2") (pinfunction "2_2") (pintype "passive"))
      (node (ref "R2") (pin "2") (pinfunction "2_2") (pintype "passive"))
      (node (ref "R30") (pin "1") (pinfunction "1_1") (pintype "passive"))
      (node (ref "R33") (pin "1") (pinfunction "1_1") (pintype "passive"))
      (node (ref "R35") (pin "1") (pinfunction "1_1") (pintype "passive"))
      (node (ref "R37") (pin "1") (pinfunction "1_1") (pintype "passive"))
      (node (ref "R4") (pin "1") (pinfunction "1_1") (pintype "passive"))
      (node (ref "R40") (pin "1") (pinfunction "1_1") (pintype "passive"))
      (node (ref "R44") (pin "1") (pinfunction "1_1") (pintype "passive"))
      (node (ref "R46") (pin "1") (pinfunction "1_1") (pintype "passive"))
      (node (ref "R48") (pin "1") (pinfunction "1_1") (pintype "passive"))
      (node (ref "R51") (pin "1") (pinfunction "1_1") (pintype "passive"))
      (node (ref "R6") (pin "1") (pinfunction "1_1") (pintype "passive"))
      (node (ref "RIGHT") (pin "3") (pinfunction "P_3") (pintype "passive"))
      (node (ref "RIGHT") (pin "4") (pinfunction "P_4") (pintype "passive"))
      (node (ref "U$1") (pin "2") (pinfunction "GND_2") (pintype "bidirectional"))
      (node (ref "U$1") (pin "5") (pinfunction "GND_5") (pintype "bidirectional"))
      (node (ref "U1") (pin "18") (pinfunction "GND1_18") (pintype "power_in"))
      (node (ref "U1") (pin "28") (pinfunction "GND_28") (pintype "power_in"))
      (node (ref "U1") (pin "39") (pinfunction "GND2_39") (pintype "power_in"))
      (node (ref "U1") (pin "6") (pinfunction "GND_6") (pintype "power_in"))
      (node (ref "U10") (pin "4") (pinfunction "V-_4") (pintype "power_in"))
      (node (ref "U3") (pin "7") (pinfunction "VSS_7") (pintype "power_in"))
      (node (ref "U8B") (pin "7") (pinfunction "GND_7") (pintype "power_in"))
    )
    (net (code "5") (name "Net-(BATA-S)") (class "Default")
      (node (ref "BAT") (pin "1") (pinfunction "S_1") (pintype "passive"))
      (node (ref "P_SWITCH") (pin "2") (pinfunction "2_2") (pintype "bidirectional"))
    )
    (net (code "6") (name "Net-(CHAN_A-Pad1)") (class "Default")
      (node (ref "CHAN_A") (pin "1") (pinfunction "1_1") (pintype "bidirectional"))
      (node (ref "TR1") (pin "3") (pinfunction "3_3") (pintype "passive"))
    )
    (net (code "7") (name "Net-(CHAN_A-Pad3)") (class "Default")
      (node (ref "CHAN_A") (pin "3") (pinfunction "3_3") (pintype "bidirectional"))
      (node (ref "TR1") (pin "1") (pinfunction "1_1") (pintype "passive"))
    )
    (net (code "8") (name "Net-(CHAN_B-Pad1)") (class "Default")
      (node (ref "CHAN_B") (pin "1") (pinfunction "1_1") (pintype "bidirectional"))
      (node (ref "TR2") (pin "3") (pinfunction "3_3") (pintype "passive"))
    )
    (net (code "9") (name "Net-(CHAN_B-Pad3)") (class "Default")
      (node (ref "CHAN_B") (pin "3") (pinfunction "3_3") (pintype "bidirectional"))
      (node (ref "TR2") (pin "1") (pinfunction "1_1") (pintype "passive"))
    )
    (net (code "10") (name "Net-(CRYSTAL-CRYSTAL_1)") (class "Default")
      (node (ref "C15") (pin "1") (pinfunction "1_1") (pintype "passive"))
      (node (ref "CRYSTAL") (pin "1") (pinfunction "CRYSTAL_1_1") (pintype "bidirectional"))
      (node (ref "U1") (pin "7") (pinfunction "XTAL2_7") (pintype "bidirectional"))
    )
    (net (code "11") (name "Net-(CRYSTAL-CRYSTAL_2)") (class "Default")
      (node (ref "C16") (pin "1") (pinfunction "1_1") (pintype "passive"))
      (node (ref "CRYSTAL") (pin "3") (pinfunction "CRYSTAL_2_3") (pintype "bidirectional"))
      (node (ref "U1") (pin "8") (pinfunction "XTAL1_8") (pintype "bidirectional"))
    )
    (net (code "12") (name "Net-(DC_IN-CENTER_PIN)") (class "Default")
      (node (ref "DC_IN") (pin "1") (pinfunction "CENTER_PIN_1") (pintype "bidirectional"))
      (node (ref "P_SWITCH") (pin "1") (pinfunction "1_1") (pintype "bidirectional"))
    )
    (net (code "13") (name "Net-(F1-Pad1)") (class "Default")
      (node (ref "F1") (pin "1") (pinfunction "1_1") (pintype "bidirectional"))
      (node (ref "P_SWITCH") (pin "3") (pinfunction "3_3") (pintype "bidirectional"))
    )
    (net (code "14") (name "Net-(LCD1-A)") (class "Default")
      (node (ref "BRIGHT") (pin "A") (pinfunction "A_A") (pintype "passive"))
      (node (ref "BRIGHT") (pin "S") (pinfunction "S_S") (pintype "passive"))
      (node (ref "LCD1") (pin "15") (pinfunction "A_15") (pintype "input"))
    )
    (net (code "15") (name "Net-(LCD1-K)") (class "Default")
      (node (ref "LCD1") (pin "16") (pinfunction "K_16") (pintype "input"))
      (node (ref "Q8") (pin "C") (pinfunction "C_C") (pintype "passive"))
    )
    (net (code "16") (name "Net-(LCD1-VO)") (class "Default")
      (node (ref "CONTR.") (pin "S") (pinfunction "S_S") (pintype "passive"))
      (node (ref "LCD1") (pin "3") (pinfunction "VO_3") (pintype "input"))
    )
    (net (code "17") (name "Net-(LED_CH_A-PadA)") (class "Default")
      (node (ref "LED_CH_A") (pin "A") (pinfunction "A_A") (pintype "passive"))
      (node (ref "R54") (pin "1") (pinfunction "1_1") (pintype "passive"))
    )
    (net (code "18") (name "Net-(LED_CH_B-PadA)") (class "Default")
      (node (ref "LED_CH_B") (pin "A") (pinfunction "A_A") (pintype "passive"))
      (node (ref "R53") (pin "1") (pinfunction "1_1") (pintype "passive"))
    )
    (net (code "19") (name "Net-(LED_POWER-PadA)") (class "Default")
      (node (ref "LED_POWER") (pin "A") (pinfunction "A_A") (pintype "passive"))
      (node (ref "R60") (pin "1") (pinfunction "1_1") (pintype "passive"))
    )
    (net (code "20") (name "Net-(MULTI-E)") (class "Default")
      (node (ref "MULTI") (pin "3") (pinfunction "E_3") (pintype "passive"))
      (node (ref "R7") (pin "1") (pinfunction "1_1") (pintype "passive"))
    )
    (net (code "21") (name "Net-(Q1-D-Pad2)") (class "Default")
      (node (ref "Q1") (pin "2") (pinfunction "D_2") (pintype "passive"))
      (node (ref "Q1") (pin "4") (pinfunction "D_4") (pintype "passive"))
      (node (ref "TR1") (pin "4") (pinfunction "4_4") (pintype "passive"))
    )
    (net (code "22") (name "Net-(Q1-G)") (class "Default")
      (node (ref "Q1") (pin "1") (pinfunction "G_1") (pintype "passive"))
      (node (ref "R38") (pin "2") (pinfunction "2_2") (pintype "passive"))
    )
    (net (code "23") (name "Net-(Q2-D-Pad2)") (class "Default")
      (node (ref "Q2") (pin "2") (pinfunction "D_2") (pintype "passive"))
      (node (ref "Q2") (pin "4") (pinfunction "D_4") (pintype "passive"))
      (node (ref "TR1") (pin "6") (pinfunction "6_6") (pintype "passive"))
    )
    (net (code "24") (name "Net-(Q2-G)") (class "Default")
      (node (ref "Q2") (pin "1") (pinfunction "G_1") (pintype "passive"))
      (node (ref "R41") (pin "2") (pinfunction "2_2") (pintype "passive"))
    )
    (net (code "25") (name "Net-(Q3-D-Pad2)") (class "Default")
      (node (ref "Q3") (pin "2") (pinfunction "D_2") (pintype "passive"))
      (node (ref "Q3") (pin "4") (pinfunction "D_4") (pintype "passive"))
      (node (ref "TR1") (pin "5") (pinfunction "5_5") (pintype "passive"))
    )
    (net (code "26") (name "Net-(Q3-G)") (class "Default")
      (node (ref "C39") (pin "1") (pinfunction "1_1") (pintype "passive"))
      (node (ref "Q3") (pin "1") (pinfunction "G_1") (pintype "passive"))
      (node (ref "R39") (pin "2") (pinfunction "2_2") (pintype "passive"))
    )
    (net (code "27") (name "Net-(Q4-D-Pad2)") (class "Default")
      (node (ref "Q4") (pin "2") (pinfunction "D_2") (pintype "passive"))
      (node (ref "Q4") (pin "4") (pinfunction "D_4") (pintype "passive"))
      (node (ref "TR2") (pin "4") (pinfunction "4_4") (pintype "passive"))
    )
    (net (code "28") (name "Net-(Q4-G)") (class "Default")
      (node (ref "Q4") (pin "1") (pinfunction "G_1") (pintype "passive"))
      (node (ref "R49") (pin "2") (pinfunction "2_2") (pintype "passive"))
    )
    (net (code "29") (name "Net-(Q5-D-Pad2)") (class "Default")
      (node (ref "Q5") (pin "2") (pinfunction "D_2") (pintype "passive"))
      (node (ref "Q5") (pin "4") (pinfunction "D_4") (pintype "passive"))
      (node (ref "TR2") (pin "6") (pinfunction "6_6") (pintype "passive"))
    )
    (net (code "30") (name "Net-(Q5-G)") (class "Default")
      (node (ref "Q5") (pin "1") (pinfunction "G_1") (pintype "passive"))
      (node (ref "R52") (pin "2") (pinfunction "2_2") (pintype "passive"))
    )
    (net (code "31") (name "Net-(Q6-D-Pad2)") (class "Default")
      (node (ref "Q6") (pin "2") (pinfunction "D_2") (pintype "passive"))
      (node (ref "Q6") (pin "4") (pinfunction "D_4") (pintype "passive"))
      (node (ref "TR2") (pin "5") (pinfunction "5_5") (pintype "passive"))
    )
    (net (code "32") (name "Net-(Q6-G)") (class "Default")
      (node (ref "C40") (pin "1") (pinfunction "1_1") (pintype "passive"))
      (node (ref "Q6") (pin "1") (pinfunction "G_1") (pintype "passive"))
      (node (ref "R50") (pin "2") (pinfunction "2_2") (pintype "passive"))
    )
    (net (code "33") (name "Net-(Q7-PadB)") (class "Default")
      (node (ref "Q7") (pin "B") (pinfunction "B_B") (pintype "passive"))
      (node (ref "R56") (pin "1") (pinfunction "1_1") (pintype "passive"))
    )
    (net (code "34") (name "Net-(Q7-PadC)") (class "Default")
      (node (ref "Q7") (pin "C") (pinfunction "C_C") (pintype "passive"))
      (node (ref "Q8") (pin "B") (pinfunction "B_B") (pintype "passive"))
      (node (ref "R57") (pin "2") (pinfunction "2_2") (pintype "passive"))
    )
    (net (code "35") (name "Net-(U1-(ADC2)PA2)") (class "Default")
      (node (ref "R4") (pin "2") (pinfunction "2_2") (pintype "passive"))
      (node (ref "U1") (pin "35") (pinfunction "(ADC2)PA2_35") (pintype "bidirectional"))
    )
    (net (code "36") (name "Net-(U1-(ADC3)PA3)") (class "Default")
      (node (ref "R5") (pin "1") (pinfunction "1_1") (pintype "passive"))
      (node (ref "R6") (pin "2") (pinfunction "2_2") (pintype "passive"))
      (node (ref "U1") (pin "34") (pinfunction "(ADC3)PA3_34") (pintype "bidirectional"))
    )
    (net (code "37") (name "Net-(U1-(ADC6)PA6)") (class "Default")
      (node (ref "R2") (pin "1") (pinfunction "1_1") (pintype "passive"))
      (node (ref "U1") (pin "31") (pinfunction "(ADC6)PA6_31") (pintype "bidirectional"))
    )
    (net (code "38") (name "Net-(U1-(ADC7)PA7)") (class "Default")
      (node (ref "R1") (pin "1") (pinfunction "1_1") (pintype "passive"))
      (node (ref "U1") (pin "30") (pinfunction "(ADC7)PA7_30") (pintype "bidirectional"))
    )
    (net (code "39") (name "Net-(U1-(RXD)PD0)") (class "Default")
      (node (ref "U1") (pin "9") (pinfunction "(RXD)PD0_9") (pintype "bidirectional"))
      (node (ref "UART") (pin "2") (pinfunction "2_2") (pintype "passive"))
    )
    (net (code "40") (name "Net-(U1-(TXD)PD1)") (class "Default")
      (node (ref "U1") (pin "10") (pinfunction "(TXD)PD1_10") (pintype "bidirectional"))
      (node (ref "UART") (pin "1") (pinfunction "1_1") (pintype "passive"))
    )
    (net (code "41") (name "Net-(U3A-A)") (class "Default")
      (node (ref "C7") (pin "1") (pinfunction "1_1") (pintype "passive"))
      (node (ref "MENU") (pin "1") (pinfunction "S_1") (pintype "passive"))
      (node (ref "MENU") (pin "2") (pinfunction "S_2") (pintype "passive"))
      (node (ref "R11") (pin "2") (pinfunction "2_2") (pintype "passive"))
      (node (ref "U3") (pin "1") (pinfunction "A_1") (pintype "tri_state"))
    )
    (net (code "42") (name "Net-(U3B-A)") (class "Default")
      (node (ref "C5") (pin "1") (pinfunction "1_1") (pintype "passive"))
      (node (ref "R10") (pin "2") (pinfunction "2_2") (pintype "passive"))
      (node (ref "RIGHT") (pin "1") (pinfunction "S_1") (pintype "passive"))
      (node (ref "RIGHT") (pin "2") (pinfunction "S_2") (pintype "passive"))
      (node (ref "U3") (pin "4") (pinfunction "A_4") (pintype "tri_state"))
    )
    (net (code "43") (name "Net-(U3C-A)") (class "Default")
      (node (ref "C4") (pin "1") (pinfunction "1_1") (pintype "passive"))
      (node (ref "OK") (pin "1") (pinfunction "S_1") (pintype "passive"))
      (node (ref "OK") (pin "2") (pinfunction "S_2") (pintype "passive"))
      (node (ref "R9") (pin "2") (pinfunction "2_2") (pintype "passive"))
      (node (ref "U3") (pin "8") (pinfunction "A_8") (pintype "tri_state"))
    )
    (net (code "44") (name "Net-(U3D-A)") (class "Default")
      (node (ref "C3") (pin "1") (pinfunction "1_1") (pintype "passive"))
      (node (ref "LEFT") (pin "1") (pinfunction "S_1") (pintype "passive"))
      (node (ref "LEFT") (pin "2") (pinfunction "S_2") (pintype "passive"))
      (node (ref "R8") (pin "2") (pinfunction "2_2") (pintype "passive"))
      (node (ref "U3") (pin "11") (pinfunction "A_11") (pintype "tri_state"))
    )
    (net (code "45") (name "Net-(U8B-VOUT_A)") (class "Default")
      (node (ref "R42") (pin "1") (pinfunction "1_1") (pintype "passive"))
      (node (ref "U8B") (pin "8") (pinfunction "VOUT_A_8") (pintype "output"))
    )
    (net (code "46") (name "Net-(U8B-VOUT_B)") (class "Default")
      (node (ref "R31") (pin "1") (pinfunction "1_1") (pintype "passive"))
      (node (ref "U8B") (pin "5") (pinfunction "VOUT_B_5") (pintype "output"))
    )
    (net (code "47") (name "Net-(U10A-+IN)") (class "Default")
      (node (ref "R31") (pin "2") (pinfunction "2_2") (pintype "passive"))
      (node (ref "R32") (pin "1") (pinfunction "1_1") (pintype "passive"))
      (node (ref "R33") (pin "2") (pinfunction "2_2") (pintype "passive"))
      (node (ref "U10") (pin "3") (pinfunction "+IN_3") (pintype "input"))
    )
    (net (code "48") (name "Net-(U10A--IN)") (class "Default")
      (node (ref "R34") (pin "1") (pinfunction "1_1") (pintype "passive"))
      (node (ref "R35") (pin "2") (pinfunction "2_2") (pintype "passive"))
      (node (ref "R36") (pin "1") (pinfunction "1_1") (pintype "passive"))
      (node (ref "U10") (pin "2") (pinfunction "-IN_2") (pintype "input"))
    )
    (net (code "49") (name "Net-(U10A-OUT)") (class "Default")
      (node (ref "R36") (pin "2") (pinfunction "2_2") (pintype "passive"))
      (node (ref "R39") (pin "1") (pinfunction "1_1") (pintype "passive"))
      (node (ref "U10") (pin "1") (pinfunction "OUT_1") (pintype "output"))
    )
    (net (code "50") (name "Net-(U10B-+IN)") (class "Default")
      (node (ref "R42") (pin "2") (pinfunction "2_2") (pintype "passive"))
      (node (ref "R43") (pin "1") (pinfunction "1_1") (pintype "passive"))
      (node (ref "R44") (pin "2") (pinfunction "2_2") (pintype "passive"))
      (node (ref "U10") (pin "5") (pinfunction "+IN_5") (pintype "input"))
    )
    (net (code "51") (name "Net-(U10B--IN)") (class "Default")
      (node (ref "R45") (pin "1") (pinfunction "1_1") (pintype "passive"))
      (node (ref "R46") (pin "2") (pinfunction "2_2") (pintype "passive"))
      (node (ref "R47") (pin "1") (pinfunction "1_1") (pintype "passive"))
      (node (ref "U10") (pin "6") (pinfunction "-IN_6") (pintype "input"))
    )
    (net (code "52") (name "Net-(U10B-OUT)") (class "Default")
      (node (ref "R47") (pin "2") (pinfunction "2_2") (pintype "passive"))
      (node (ref "R50") (pin "1") (pinfunction "1_1") (pintype "passive"))
      (node (ref "U10") (pin "7") (pinfunction "OUT_7") (pintype "output"))
    )
    (net (code "53") (name "PA0") (class "Default")
      (node (ref "Q1") (pin "3") (pinfunction "S_3") (pintype "passive"))
      (node (ref "Q2") (pin "3") (pinfunction "S_3") (pintype "passive"))
      (node (ref "Q4") (pin "3") (pinfunction "S_3") (pintype "passive"))
      (node (ref "Q5") (pin "3") (pinfunction "S_3") (pintype "passive"))
      (node (ref "R30") (pin "2") (pinfunction "2_2") (pintype "passive"))
      (node (ref "U1") (pin "37") (pinfunction "(ADC0)PA0_37") (pintype "bidirectional"))
    )
    (net (code "54") (name "PA1") (class "Default")
      (node (ref "MULTI") (pin "2") (pinfunction "S_2") (pintype "passive"))
      (node (ref "U1") (pin "36") (pinfunction "(ADC1)PA1_36") (pintype "bidirectional"))
    )
    (net (code "55") (name "PA4") (class "Default")
      (node (ref "LEVEL_A") (pin "2") (pinfunction "S_2") (pintype "passive"))
      (node (ref "U1") (pin "33") (pinfunction "(ADC4)PA4_33") (pintype "bidirectional"))
    )
    (net (code "56") (name "PA5") (class "Default")
      (node (ref "LEVEL_B") (pin "2") (pinfunction "S_2") (pintype "passive"))
      (node (ref "U1") (pin "32") (pinfunction "(ADC5)PA5_32") (pintype "bidirectional"))
    )
    (net (code "57") (name "PB0") (class "Default")
      (node (ref "R48") (pin "2") (pinfunction "2_2") (pintype "passive"))
      (node (ref "R49") (pin "1") (pinfunction "1_1") (pintype "passive"))
      (node (ref "U1") (pin "40") (pinfunction "(T0/XCK)PB0_40") (pintype "bidirectional"))
    )
    (net (code "58") (name "PB1") (class "Default")
      (node (ref "R51") (pin "2") (pinfunction "2_2") (pintype "passive"))
      (node (ref "R52") (pin "1") (pinfunction "1_1") (pintype "passive"))
      (node (ref "U1") (pin "41") (pinfunction "(T1)PB1_41") (pintype "bidirectional"))
    )
    (net (code "59") (name "PB2") (class "Default")
      (node (ref "R37") (pin "2") (pinfunction "2_2") (pintype "passive"))
      (node (ref "R38") (pin "1") (pinfunction "1_1") (pintype "passive"))
      (node (ref "U1") (pin "42") (pinfunction "(AIN0/INT2)PB2_42") (pintype "bidirectional"))
    )
    (net (code "60") (name "PB3") (class "Default")
      (node (ref "R40") (pin "2") (pinfunction "2_2") (pintype "passive"))
      (node (ref "R41") (pin "1") (pinfunction "1_1") (pintype "passive"))
      (node (ref "U1") (pin "43") (pinfunction "(AIN1/OC0)PB3_43") (pintype "bidirectional"))
    )
    (net (code "61") (name "PB5") (class "Default")
      (node (ref "ISP1") (pin "4") (pinfunction "MOSI_4") (pintype "output"))
      (node (ref "U1") (pin "1") (pinfunction "(MOSI)PB5_1") (pintype "bidirectional"))
      (node (ref "U8B") (pin "3") (pinfunction "D_IN_3") (pintype "input"))
    )
    (net (code "62") (name "PB6") (class "Default")
      (node (ref "ISP1") (pin "1") (pinfunction "MISO_1") (pintype "input"))
      (node (ref "U1") (pin "2") (pinfunction "(MISO)PB6_2") (pintype "bidirectional"))
    )
    (net (code "63") (name "PB7") (class "Default")
      (node (ref "ISP1") (pin "3") (pinfunction "SCK_3") (pintype "output"))
      (node (ref "U1") (pin "3") (pinfunction "(SCK)PB7_3") (pintype "bidirectional"))
      (node (ref "U8B") (pin "2") (pinfunction "SCK_2") (pintype "input"))
    )
    (net (code "64") (name "PC0") (class "Default")
      (node (ref "U1") (pin "19") (pinfunction "PC0(SCL)_19") (pintype "bidirectional"))
      (node (ref "U3") (pin "12") (pinfunction "C_12") (pintype "input"))
      (node (ref "U3") (pin "13") (pinfunction "C_13") (pintype "input"))
      (node (ref "U3") (pin "5") (pinfunction "C_5") (pintype "input"))
      (node (ref "U3") (pin "6") (pinfunction "C_6") (pintype "input"))
    )
    (net (code "65") (name "PC1") (class "Default")
      (node (ref "LCD1") (pin "5") (pinfunction "RW_5") (pintype "input"))
      (node (ref "U1") (pin "20") (pinfunction "PC1(SDA)_20") (pintype "bidirectional"))
    )
    (net (code "66") (name "PC2") (class "Default")
      (node (ref "LCD1") (pin "6") (pinfunction "E_6") (pintype "input"))
      (node (ref "U1") (pin "21") (pinfunction "(TCK)PC2_21") (pintype "bidirectional"))
    )
    (net (code "67") (name "PC3") (class "Default")
      (node (ref "LCD1") (pin "4") (pinfunction "RS_4") (pintype "input"))
      (node (ref "U1") (pin "22") (pinfunction "(TMS)PC3_22") (pintype "bidirectional"))
    )
    (net (code "68") (name "PC4") (class "Default")
      (node (ref "LCD1") (pin "11") (pinfunction "DB4_11") (pintype "bidirectional"))
      (node (ref "U1") (pin "23") (pinfunction "(TDO)PC4_23") (pintype "bidirectional"))
      (node (ref "U3") (pin "10") (pinfunction "B_10") (pintype "tri_state"))
    )
    (net (code "69") (name "PC5") (class "Default")
      (node (ref "LCD1") (pin "12") (pinfunction "DB5_12") (pintype "bidirectional"))
      (node (ref "U1") (pin "24") (pinfunction "(TDI)PC5_24") (pintype "bidirectional"))
      (node (ref "U3") (pin "9") (pinfunction "B_9") (pintype "tri_state"))
    )
    (net (code "70") (name "PC6") (class "Default")
      (node (ref "LCD1") (pin "13") (pinfunction "DB6_13") (pintype "bidirectional"))
      (node (ref "U1") (pin "25") (pinfunction "(TOSC1)PC6_25") (pintype "bidirectional"))
      (node (ref "U3") (pin "3") (pinfunction "B_3") (pintype "tri_state"))
    )
    (net (code "71") (name "PC7") (class "Default")
      (node (ref "LCD1") (pin "14") (pinfunction "DB7_14") (pintype "bidirectional"))
      (node (ref "U1") (pin "26") (pinfunction "(TOSC2)PC7_26") (pintype "bidirectional"))
      (node (ref "U3") (pin "2") (pinfunction "B_2") (pintype "tri_state"))
    )
    (net (code "72") (name "PD5") (class "Default")
      (node (ref "LED_CH_B") (pin "K") (pinfunction "C_K") (pintype "passive"))
      (node (ref "U1") (pin "14") (pinfunction "(OC1A)PD5_14") (pintype "bidirectional"))
    )
    (net (code "73") (name "PD6") (class "Default")
      (node (ref "LED_CH_A") (pin "K") (pinfunction "C_K") (pintype "passive"))
      (node (ref "U1") (pin "15") (pinfunction "(ICP)PD6_15") (pintype "bidirectional"))
    )
    (net (code "74") (name "PD7") (class "Default")
      (node (ref "R56") (pin "2") (pinfunction "2_2") (pintype "passive"))
      (node (ref "U1") (pin "16") (pinfunction "(OC2)PD7_16") (pintype "bidirectional"))
    )
    (net (code "75") (name "RESET") (class "Default")
      (node (ref "C8") (pin "1") (pinfunction "1_1") (pintype "passive"))
      (node (ref "ISP1") (pin "5") (pinfunction "RST_5") (pintype "output"))
      (node (ref "R3") (pin "1") (pinfunction "1_1") (pintype "passive"))
      (node (ref "U1") (pin "4") (pinfunction "RESET_4") (pintype "input"))
    )
    (net (code "76") (name "unconnected-(CHAN_A-Pad2)") (class "Default")
      (node (ref "CHAN_A") (pin "2") (pinfunction "2_2") (pintype "bidirectional"))
    )
    (net (code "77") (name "unconnected-(CHAN_B-Pad2)") (class "Default")
      (node (ref "CHAN_B") (pin "2") (pinfunction "2_2") (pintype "bidirectional"))
    )
    (net (code "78") (name "unconnected-(DC_IN-SLEEVE_SHUNT-Pad2)") (class "Default")
      (node (ref "DC_IN") (pin "2") (pinfunction "SLEEVE_SHUNT_2") (pintype "bidirectional"))
    )
    (net (code "79") (name "unconnected-(LCD1-DB0-Pad7)") (class "Default")
      (node (ref "LCD1") (pin "7") (pinfunction "DB0_7") (pintype "bidirectional"))
    )
    (net (code "80") (name "unconnected-(LCD1-DB1-Pad8)") (class "Default")
      (node (ref "LCD1") (pin "8") (pinfunction "DB1_8") (pintype "bidirectional"))
    )
    (net (code "81") (name "unconnected-(LCD1-DB2-Pad9)") (class "Default")
      (node (ref "LCD1") (pin "9") (pinfunction "DB2_9") (pintype "bidirectional"))
    )
    (net (code "82") (name "unconnected-(LCD1-DB3-Pad10)") (class "Default")
      (node (ref "LCD1") (pin "10") (pinfunction "DB3_10") (pintype "bidirectional"))
    )
    (net (code "83") (name "unconnected-(TR1-Pad2)") (class "Default")
      (node (ref "TR1") (pin "2") (pinfunction "2_2") (pintype "passive"))
    )
    (net (code "84") (name "unconnected-(TR2-Pad2)") (class "Default")
      (node (ref "TR2") (pin "2") (pinfunction "2_2") (pintype "passive"))
    )
    (net (code "85") (name "unconnected-(U$1-TRIM-Pad4)") (class "Default")
      (node (ref "U$1") (pin "4") (pinfunction "TRIM_4") (pintype "input"))
    )
    (net (code "86") (name "unconnected-(U1-(INT0)PD2-Pad11)") (class "Default")
      (node (ref "U1") (pin "11") (pinfunction "(INT0)PD2_11") (pintype "bidirectional"))
    )
    (net (code "87") (name "unconnected-(U1-(INT1)PD3-Pad12)") (class "Default")
      (node (ref "U1") (pin "12") (pinfunction "(INT1)PD3_12") (pintype "bidirectional"))
    )
    (net (code "88") (name "unconnected-(U1-(SS)PB4-Pad44)") (class "Default")
      (node (ref "U1") (pin "44") (pinfunction "(SS)PB4_44") (pintype "bidirectional"))
    )
    (net (code "89") (name "~{CS}") (class "Default")
      (node (ref "U1") (pin "13") (pinfunction "(OC1B)PD4_13") (pintype "bidirectional"))
      (node (ref "U8B") (pin "1") (pinfunction "CS/LD_1") (pintype "input"))
    )
  )
)
